# BeagleWire_Debug_-_CRRYEK.net
KiCad netlist of a schematic drawn in EAGLE
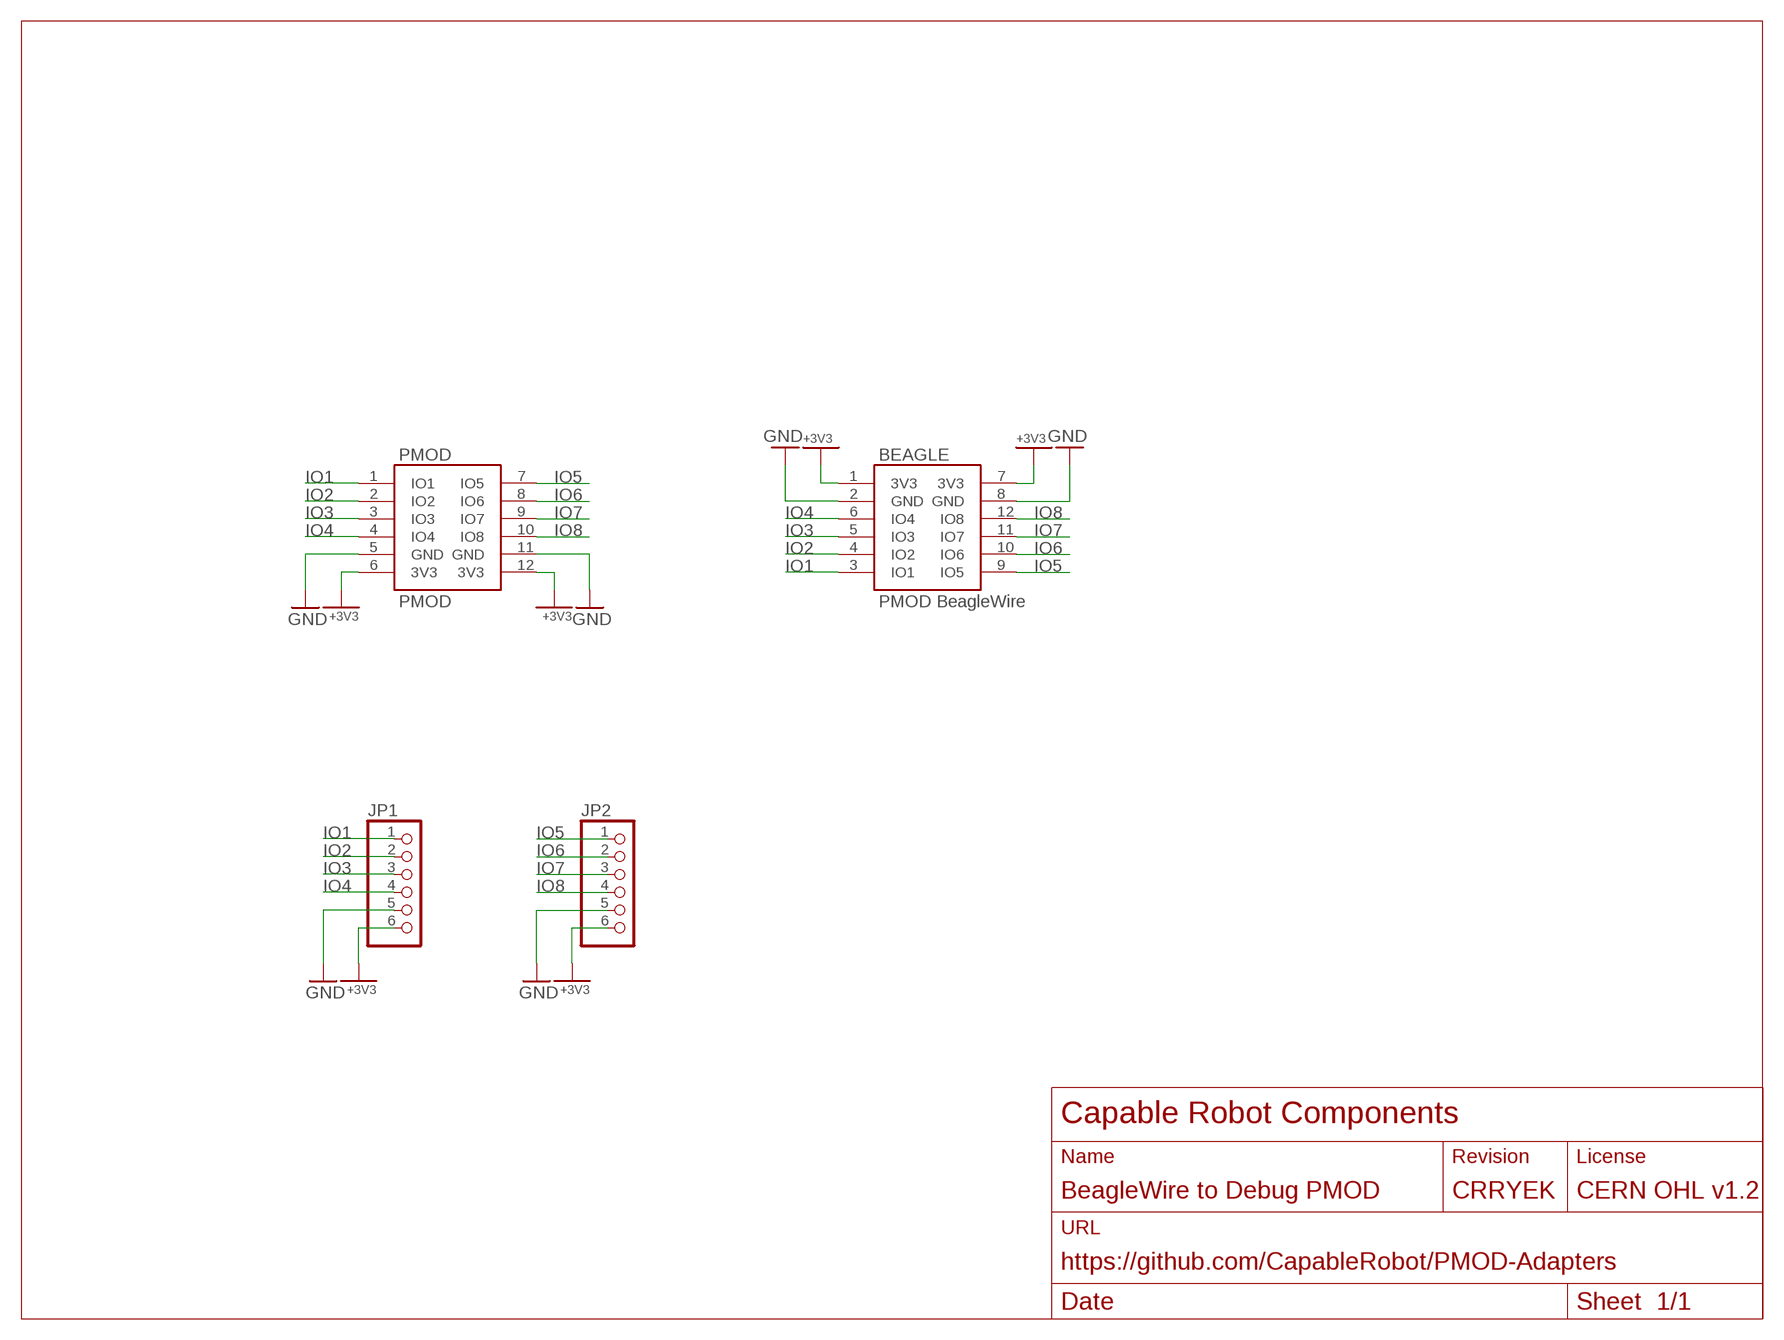
[diagram p0: schematic, sheet 1]

(export (version "E")
  (design (tool "Eeschema 10.0.6"))
  (components
    (comp (ref "BEAGLE")
      (value "PMOD-BEAGLEWIRE")
      (footprint "eagle-import:HDRRA12W64P254_2X6_1524X254X556B")
      (libsource (lib "eagle-import") (part "PMOD-BEAGLEWIRE"))
    )
    (comp (ref "JP1")
      (value "PINHD-1X6")
      (footprint "eagle-import:1X06")
      (libsource (lib "eagle-import") (part "PINHD-1X6"))
    )
    (comp (ref "JP2")
      (value "PINHD-1X6")
      (footprint "eagle-import:1X06")
      (libsource (lib "eagle-import") (part "PINHD-1X6"))
    )
    (comp (ref "PMOD")
      (value "PMOD-HOST")
      (footprint "eagle-import:HDRRAR12W64P254_2X6_1524X736X556B")
      (libsource (lib "eagle-import") (part "PMOD-HOST"))
    )
  )
  (nets
    (net (code "1") (name "+3V3") (class "Default")
      (node (ref "BEAGLE") (pin "1") (pinfunction "3V3_1") (pintype "bidirectional"))
      (node (ref "BEAGLE") (pin "7") (pinfunction "3V3_7") (pintype "bidirectional"))
      (node (ref "JP1") (pin "6") (pinfunction "6_6") (pintype "passive"))
      (node (ref "JP2") (pin "6") (pinfunction "6_6") (pintype "passive"))
      (node (ref "PMOD") (pin "12") (pinfunction "3V3_12") (pintype "bidirectional"))
      (node (ref "PMOD") (pin "6") (pinfunction "3V3_6") (pintype "bidirectional"))
    )
    (net (code "2") (name "/IO1") (class "Default")
      (node (ref "BEAGLE") (pin "3") (pinfunction "IO1_3") (pintype "bidirectional"))
      (node (ref "JP1") (pin "1") (pinfunction "1_1") (pintype "passive"))
      (node (ref "PMOD") (pin "1") (pinfunction "IO1_1") (pintype "bidirectional"))
    )
    (net (code "3") (name "/IO2") (class "Default")
      (node (ref "BEAGLE") (pin "4") (pinfunction "IO2_4") (pintype "bidirectional"))
      (node (ref "JP1") (pin "2") (pinfunction "2_2") (pintype "passive"))
      (node (ref "PMOD") (pin "2") (pinfunction "IO2_2") (pintype "bidirectional"))
    )
    (net (code "4") (name "/IO3") (class "Default")
      (node (ref "BEAGLE") (pin "5") (pinfunction "IO3_5") (pintype "bidirectional"))
      (node (ref "JP1") (pin "3") (pinfunction "3_3") (pintype "passive"))
      (node (ref "PMOD") (pin "3") (pinfunction "IO3_3") (pintype "bidirectional"))
    )
    (net (code "5") (name "/IO4") (class "Default")
      (node (ref "BEAGLE") (pin "6") (pinfunction "IO4_6") (pintype "bidirectional"))
      (node (ref "JP1") (pin "4") (pinfunction "4_4") (pintype "passive"))
      (node (ref "PMOD") (pin "4") (pinfunction "IO4_4") (pintype "bidirectional"))
    )
    (net (code "6") (name "/IO5") (class "Default")
      (node (ref "BEAGLE") (pin "9") (pinfunction "IO5_9") (pintype "bidirectional"))
      (node (ref "JP2") (pin "1") (pinfunction "1_1") (pintype "passive"))
      (node (ref "PMOD") (pin "7") (pinfunction "IO5_7") (pintype "bidirectional"))
    )
    (net (code "7") (name "/IO6") (class "Default")
      (node (ref "BEAGLE") (pin "10") (pinfunction "IO6_10") (pintype "bidirectional"))
      (node (ref "JP2") (pin "2") (pinfunction "2_2") (pintype "passive"))
      (node (ref "PMOD") (pin "8") (pinfunction "IO6_8") (pintype "bidirectional"))
    )
    (net (code "8") (name "/IO7") (class "Default")
      (node (ref "BEAGLE") (pin "11") (pinfunction "IO7_11") (pintype "bidirectional"))
      (node (ref "JP2") (pin "3") (pinfunction "3_3") (pintype "passive"))
      (node (ref "PMOD") (pin "9") (pinfunction "IO7_9") (pintype "bidirectional"))
    )
    (net (code "9") (name "/IO8") (class "Default")
      (node (ref "BEAGLE") (pin "12") (pinfunction "IO8_12") (pintype "bidirectional"))
      (node (ref "JP2") (pin "4") (pinfunction "4_4") (pintype "passive"))
      (node (ref "PMOD") (pin "10") (pinfunction "IO8_10") (pintype "bidirectional"))
    )
    (net (code "10") (name "GND") (class "Default")
      (node (ref "BEAGLE") (pin "2") (pinfunction "GND_2") (pintype "bidirectional"))
      (node (ref "BEAGLE") (pin "8") (pinfunction "GND_8") (pintype "bidirectional"))
      (node (ref "JP1") (pin "5") (pinfunction "5_5") (pintype "passive"))
      (node (ref "JP2") (pin "5") (pinfunction "5_5") (pintype "passive"))
      (node (ref "PMOD") (pin "11") (pinfunction "GND_11") (pintype "bidirectional"))
      (node (ref "PMOD") (pin "5") (pinfunction "GND_5") (pintype "bidirectional"))
    )
  )
)
